# ScopeVideoOnly.net
KiCad netlist of a schematic drawn in Altium Designer
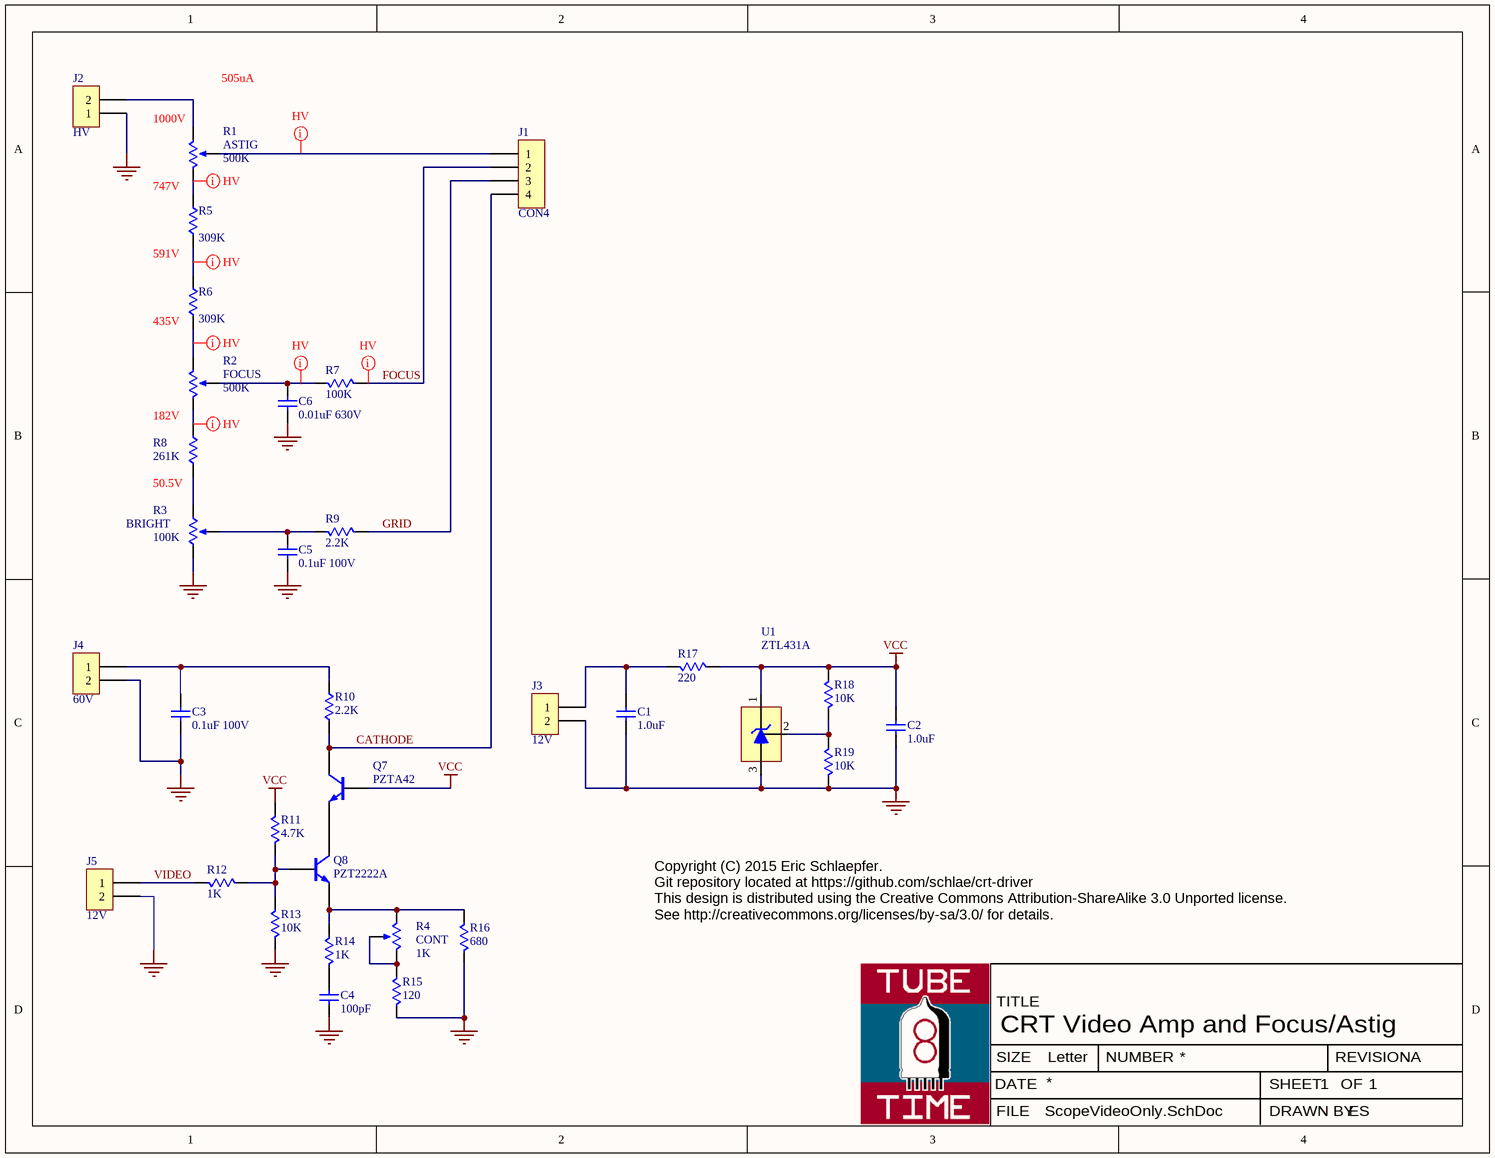
[diagram p0: ScopeVideoOnly.SchDoc]

(export (version "E")
  (design (tool "Eeschema 10.0.6"))
  (components
    (comp (ref "C1")
      (value "1.0uF")
      (footprint "G_0805[2012]")
      (description "Capacitor")
      (fields (field (name "MANUFPART") "C2012X7R1E105K125AB") (field (name "Comment") "Cap"))
      (libsource (lib "ClikCommon") (part "Cap"))
    )
    (comp (ref "C2")
      (value "1.0uF")
      (footprint "G_0805[2012]")
      (description "Capacitor")
      (fields (field (name "MANUFPART") "C2012X7R1E105K125AB") (field (name "Comment") "Cap"))
      (libsource (lib "ClikCommon") (part "Cap"))
    )
    (comp (ref "C3")
      (value "0.1uF 100V")
      (footprint "G_1206[3216]")
      (description "Capacitor")
      (fields (field (name "Comment") "Cap"))
      (libsource (lib "ClikCommon") (part "Cap"))
    )
    (comp (ref "C4")
      (value "100pF")
      (footprint "G_0805[2012]")
      (description "Capacitor")
      (fields (field (name "Comment") "Cap"))
      (libsource (lib "ClikCommon") (part "Cap"))
    )
    (comp (ref "C5")
      (value "0.1uF 100V")
      (footprint "G_1206[3216]")
      (description "Capacitor")
      (fields (field (name "Comment") "Cap"))
      (libsource (lib "ClikCommon") (part "Cap"))
    )
    (comp (ref "C6")
      (value "0.01uF 630V")
      (footprint "G_1206[3216]")
      (description "Capacitor")
      (fields (field (name "Comment") "Cap"))
      (libsource (lib "ClikCommon") (part "Cap"))
    )
    (comp (ref "J1")
      (value "CON4")
      (description "Connector, 4 pin")
      (libsource (lib "ClikConnectors") (part "CON4"))
    )
    (comp (ref "J2")
      (value "HV")
      (footprint "HDR3S156M1")
      (description "Connector, 2 pin")
      (libsource (lib "") (part "CON2_1"))
    )
    (comp (ref "J3")
      (value "12V")
      (footprint "HDR2S")
      (description "Connector, 2 pin")
      (libsource (lib "ClikConnectors") (part "CON2"))
    )
    (comp (ref "J4")
      (value "60V")
      (footprint "HDR2S")
      (description "Connector, 2 pin")
      (libsource (lib "ClikConnectors") (part "CON2"))
    )
    (comp (ref "J5")
      (value "12V")
      (footprint "HDR2S")
      (description "Connector, 2 pin")
      (libsource (lib "ClikConnectors") (part "CON2"))
    )
    (comp (ref "Q7")
      (value "PZTA42")
      (footprint "G_SOT223T")
      (description "NPN Bipolar Transistor")
      (fields (field (name "Comment") "NPN"))
      (libsource (lib "ClikCommon") (part "NPN"))
    )
    (comp (ref "Q8")
      (value "PZT2222A")
      (footprint "G_SOT223T")
      (description "NPN Bipolar Transistor")
      (fields (field (name "Comment") "NPN"))
      (libsource (lib "") (part "NPN_1"))
    )
    (comp (ref "R1")
      (value "ASTIG")
      (footprint "POT_TRIM BOURNS 3386F")
      (description "Variable Resistor")
      (fields (field (name "ALTIUM_VALUE") "500K") (field (name "MANUFPART") "3386F-1-504LF"))
      (libsource (lib "ClikCommon") (part "Pot"))
    )
    (comp (ref "R2")
      (value "FOCUS")
      (footprint "POT_TRIM BOURNS 3386F")
      (description "Variable Resistor")
      (fields (field (name "ALTIUM_VALUE") "500K") (field (name "MANUFPART") "3386F-1-504LF"))
      (libsource (lib "ClikCommon") (part "Pot"))
    )
    (comp (ref "R3")
      (value "BRIGHT")
      (footprint "POT_TRIM BOURNS 3386F")
      (description "Variable Resistor")
      (fields (field (name "ALTIUM_VALUE") "100K") (field (name "MANUFPART") "3386F-1-104LF"))
      (libsource (lib "ClikCommon") (part "Pot"))
    )
    (comp (ref "R4")
      (value "CONT")
      (footprint "POT_TRIM BOURNS 3386F")
      (description "Variable Resistor")
      (fields (field (name "ALTIUM_VALUE") "1K") (field (name "MANUFPART") "3386F-1-102LF"))
      (libsource (lib "ClikCommon") (part "Pot"))
    )
    (comp (ref "R5")
      (value "309K")
      (footprint "G_1206[3216]")
      (description "Resistor")
      (fields (field (name "MANUFPART") "ERJ-8ENF3093V") (field (name "Comment") "Res1"))
      (libsource (lib "ClikCommon") (part "Res"))
    )
    (comp (ref "R6")
      (value "309K")
      (footprint "G_1206[3216]")
      (description "Resistor")
      (fields (field (name "MANUFPART") "ERJ-8ENF3093V") (field (name "Comment") "Res1"))
      (libsource (lib "ClikCommon") (part "Res"))
    )
    (comp (ref "R7")
      (value "100K")
      (footprint "G_0805[2012]")
      (description "Resistor")
      (fields (field (name "MANUFPART") "CRCW0805100KFKEA") (field (name "Comment") "Res1"))
      (libsource (lib "ClikCommon") (part "Res"))
    )
    (comp (ref "R8")
      (value "261K")
      (footprint "G_1206[3216]")
      (description "Resistor")
      (fields (field (name "MANUFPART") "CRCW1206261KFKEA") (field (name "Comment") "Res1"))
      (libsource (lib "ClikCommon") (part "Res"))
    )
    (comp (ref "R9")
      (value "2.2K")
      (footprint "G_0805[2012]")
      (description "Resistor")
      (fields (field (name "MANUFPART") "ERJ-6ENF2201V") (field (name "Comment") "Res1"))
      (libsource (lib "ClikCommon") (part "Res"))
    )
    (comp (ref "R10")
      (value "2.2K")
      (footprint "G_1206[3216]")
      (description "Resistor")
      (fields (field (name "MANUFPART") "CRCW12062K20FKEA") (field (name "Comment") "Res1"))
      (libsource (lib "ClikCommon") (part "Res"))
    )
    (comp (ref "R11")
      (value "4.7K")
      (footprint "G_0805[2012]")
      (description "Resistor")
      (fields (field (name "MANUFPART") "CRCW08054K70FKEA") (field (name "Comment") "Res1"))
      (libsource (lib "ClikCommon") (part "Res"))
    )
    (comp (ref "R12")
      (value "1K")
      (footprint "G_0805[2012]")
      (description "Resistor")
      (fields (field (name "MANUFPART") "CRCW08051K00JNEA") (field (name "Comment") "Res1"))
      (libsource (lib "ClikCommon") (part "Res"))
    )
    (comp (ref "R13")
      (value "10K")
      (footprint "G_0805[2012]")
      (description "Resistor")
      (fields (field (name "MANUFPART") "CRCW080510K0FKEB") (field (name "Comment") "Res1"))
      (libsource (lib "ClikCommon") (part "Res"))
    )
    (comp (ref "R14")
      (value "1K")
      (footprint "G_0805[2012]")
      (description "Resistor")
      (fields (field (name "MANUFPART") "CRCW08051K00JNEA") (field (name "Comment") "Res1"))
      (libsource (lib "ClikCommon") (part "Res"))
    )
    (comp (ref "R15")
      (value "120")
      (footprint "G_0805[2012]")
      (description "Resistor")
      (fields (field (name "MANUFPART") "CRCW0805120RFKEA") (field (name "Comment") "Res1"))
      (libsource (lib "ClikCommon") (part "Res"))
    )
    (comp (ref "R16")
      (value "680")
      (footprint "G_0805[2012]")
      (description "Resistor")
      (fields (field (name "MANUFPART") "CRCW0805680RFKEA") (field (name "Comment") "Res1"))
      (libsource (lib "ClikCommon") (part "Res"))
    )
    (comp (ref "R17")
      (value "220")
      (footprint "G_0805[2012]")
      (description "Resistor")
      (fields (field (name "MANUFPART") "CRCW0805220RFKEA") (field (name "Comment") "Res1"))
      (libsource (lib "ClikCommon") (part "Res"))
    )
    (comp (ref "R18")
      (value "10K")
      (footprint "G_0805[2012]")
      (description "Resistor")
      (fields (field (name "MANUFPART") "CRCW080510K0FKEB") (field (name "Comment") "Res1"))
      (libsource (lib "ClikCommon") (part "Res"))
    )
    (comp (ref "R19")
      (value "10K")
      (footprint "G_0805[2012]")
      (description "Resistor")
      (fields (field (name "MANUFPART") "CRCW080510K0FKEB") (field (name "Comment") "Res1"))
      (libsource (lib "ClikCommon") (part "Res"))
    )
    (comp (ref "U1")
      (value "ZTL431A")
      (footprint "G_SOT23")
      (description "Adjustable Shunt Reg")
      (fields (field (name "MANUFPART") "ZTL431AFFTA"))
      (libsource (lib "ClikIC") (part "TL431"))
    )
  )
  (nets
    (net (code "1") (name "/CATHODE") (class "Default")
      (node (ref "J1") (pin "4") (pinfunction "4_4") (pintype "passive"))
      (node (ref "Q7") (pin "C") (pinfunction "C_C") (pintype "passive"))
      (node (ref "R10") (pin "1") (pinfunction "1_1") (pintype "passive"))
    )
    (net (code "2") (name "/FOCUS") (class "Default")
      (node (ref "J1") (pin "2") (pinfunction "2_2") (pintype "passive"))
      (node (ref "R7") (pin "1") (pinfunction "1_1") (pintype "passive"))
    )
    (net (code "3") (name "/GRID") (class "Default")
      (node (ref "J1") (pin "3") (pinfunction "3_3") (pintype "passive"))
      (node (ref "R9") (pin "1") (pinfunction "1_1") (pintype "passive"))
    )
    (net (code "4") (name "/VIDEO") (class "Default")
      (node (ref "J5") (pin "1") (pinfunction "1_1") (pintype "passive"))
      (node (ref "R12") (pin "1") (pinfunction "1_1") (pintype "passive"))
    )
    (net (code "5") (name "GND") (class "Default")
      (node (ref "C1") (pin "1") (pinfunction "1_1") (pintype "passive"))
      (node (ref "C2") (pin "1") (pinfunction "1_1") (pintype "passive"))
      (node (ref "C3") (pin "2") (pinfunction "2_2") (pintype "passive"))
      (node (ref "C4") (pin "2") (pinfunction "2_2") (pintype "passive"))
      (node (ref "C5") (pin "2") (pinfunction "2_2") (pintype "passive"))
      (node (ref "C6") (pin "2") (pinfunction "2_2") (pintype "passive"))
      (node (ref "J2") (pin "1") (pinfunction "1_1") (pintype "passive"))
      (node (ref "J3") (pin "2") (pinfunction "2_2") (pintype "passive"))
      (node (ref "J4") (pin "2") (pinfunction "2_2") (pintype "passive"))
      (node (ref "J5") (pin "2") (pinfunction "2_2") (pintype "passive"))
      (node (ref "R13") (pin "2") (pinfunction "2_2") (pintype "passive"))
      (node (ref "R15") (pin "2") (pinfunction "2_2") (pintype "passive"))
      (node (ref "R16") (pin "2") (pinfunction "2_2") (pintype "passive"))
      (node (ref "R19") (pin "2") (pinfunction "2_2") (pintype "passive"))
      (node (ref "R3") (pin "1") (pinfunction "TOP_1") (pintype "passive"))
      (node (ref "U1") (pin "3") (pinfunction "A_3") (pintype "passive"))
    )
    (net (code "6") (name "Net-(C1-Pad2)") (class "Default")
      (node (ref "C1") (pin "2") (pinfunction "2_2") (pintype "passive"))
      (node (ref "J3") (pin "1") (pinfunction "1_1") (pintype "passive"))
      (node (ref "R17") (pin "2") (pinfunction "2_2") (pintype "passive"))
    )
    (net (code "7") (name "Net-(C3-Pad1)") (class "Default")
      (node (ref "C3") (pin "1") (pinfunction "1_1") (pintype "passive"))
      (node (ref "J4") (pin "1") (pinfunction "1_1") (pintype "passive"))
      (node (ref "R10") (pin "2") (pinfunction "2_2") (pintype "passive"))
    )
    (net (code "8") (name "Net-(C4-Pad1)") (class "Default")
      (node (ref "C4") (pin "1") (pinfunction "1_1") (pintype "passive"))
      (node (ref "R14") (pin "2") (pinfunction "2_2") (pintype "passive"))
    )
    (net (code "9") (name "Net-(Q7-PadE)") (class "Default")
      (node (ref "Q7") (pin "E") (pinfunction "E_E") (pintype "passive"))
      (node (ref "Q8") (pin "C") (pinfunction "C_C") (pintype "passive"))
    )
    (net (code "10") (name "Net-(Q8-PadB)") (class "Default")
      (node (ref "Q8") (pin "B") (pinfunction "B_B") (pintype "passive"))
      (node (ref "R11") (pin "2") (pinfunction "2_2") (pintype "passive"))
      (node (ref "R12") (pin "2") (pinfunction "2_2") (pintype "passive"))
      (node (ref "R13") (pin "1") (pinfunction "1_1") (pintype "passive"))
    )
    (net (code "11") (name "Net-(R1-BOT)") (class "Default")
      (node (ref "R1") (pin "2") (pinfunction "BOT_2") (pintype "passive"))
      (node (ref "R5") (pin "2") (pinfunction "2_2") (pintype "passive"))
    )
    (net (code "12") (name "Net-(R1-TAP)") (class "Default")
      (node (ref "J1") (pin "1") (pinfunction "1_1") (pintype "passive"))
      (node (ref "R1") (pin "3") (pinfunction "TAP_3") (pintype "passive"))
    )
    (net (code "13") (name "Net-(R1-TOP)") (class "Default")
      (node (ref "J2") (pin "2") (pinfunction "2_2") (pintype "passive"))
      (node (ref "R1") (pin "1") (pinfunction "TOP_1") (pintype "passive"))
    )
    (net (code "14") (name "Net-(R2-BOT)") (class "Default")
      (node (ref "R2") (pin "2") (pinfunction "BOT_2") (pintype "passive"))
      (node (ref "R8") (pin "2") (pinfunction "2_2") (pintype "passive"))
    )
    (net (code "15") (name "Net-(R2-TAP)") (class "Default")
      (node (ref "C6") (pin "1") (pinfunction "1_1") (pintype "passive"))
      (node (ref "R2") (pin "3") (pinfunction "TAP_3") (pintype "passive"))
      (node (ref "R7") (pin "2") (pinfunction "2_2") (pintype "passive"))
    )
    (net (code "16") (name "Net-(R2-TOP)") (class "Default")
      (node (ref "R2") (pin "1") (pinfunction "TOP_1") (pintype "passive"))
      (node (ref "R6") (pin "1") (pinfunction "1_1") (pintype "passive"))
    )
    (net (code "17") (name "Net-(R3-BOT)") (class "Default")
      (node (ref "R3") (pin "2") (pinfunction "BOT_2") (pintype "passive"))
      (node (ref "R8") (pin "1") (pinfunction "1_1") (pintype "passive"))
    )
    (net (code "18") (name "Net-(R3-TAP)") (class "Default")
      (node (ref "C5") (pin "1") (pinfunction "1_1") (pintype "passive"))
      (node (ref "R3") (pin "3") (pinfunction "TAP_3") (pintype "passive"))
      (node (ref "R9") (pin "2") (pinfunction "2_2") (pintype "passive"))
    )
    (net (code "19") (name "Net-(R4-BOT)") (class "Default")
      (node (ref "Q8") (pin "E") (pinfunction "E_E") (pintype "passive"))
      (node (ref "R14") (pin "1") (pinfunction "1_1") (pintype "passive"))
      (node (ref "R16") (pin "1") (pinfunction "1_1") (pintype "passive"))
      (node (ref "R4") (pin "2") (pinfunction "BOT_2") (pintype "passive"))
    )
    (net (code "20") (name "Net-(R4-TAP)") (class "Default")
      (node (ref "R15") (pin "1") (pinfunction "1_1") (pintype "passive"))
      (node (ref "R4") (pin "1") (pinfunction "TOP_1") (pintype "passive"))
      (node (ref "R4") (pin "3") (pinfunction "TAP_3") (pintype "passive"))
    )
    (net (code "21") (name "Net-(R5-Pad1)") (class "Default")
      (node (ref "R5") (pin "1") (pinfunction "1_1") (pintype "passive"))
      (node (ref "R6") (pin "2") (pinfunction "2_2") (pintype "passive"))
    )
    (net (code "22") (name "Net-(U1-REF)") (class "Default")
      (node (ref "R18") (pin "2") (pinfunction "2_2") (pintype "passive"))
      (node (ref "R19") (pin "1") (pinfunction "1_1") (pintype "passive"))
      (node (ref "U1") (pin "2") (pinfunction "REF_2") (pintype "passive"))
    )
    (net (code "23") (name "VCC") (class "Default")
      (node (ref "C2") (pin "2") (pinfunction "2_2") (pintype "passive"))
      (node (ref "Q7") (pin "B") (pinfunction "B_B") (pintype "passive"))
      (node (ref "R11") (pin "1") (pinfunction "1_1") (pintype "passive"))
      (node (ref "R17") (pin "1") (pinfunction "1_1") (pintype "passive"))
      (node (ref "R18") (pin "1") (pinfunction "1_1") (pintype "passive"))
      (node (ref "U1") (pin "1") (pinfunction "C_1") (pintype "passive"))
    )
  )
)
